# usb_uart.net
KiCad netlist of a schematic drawn in Altium Designer
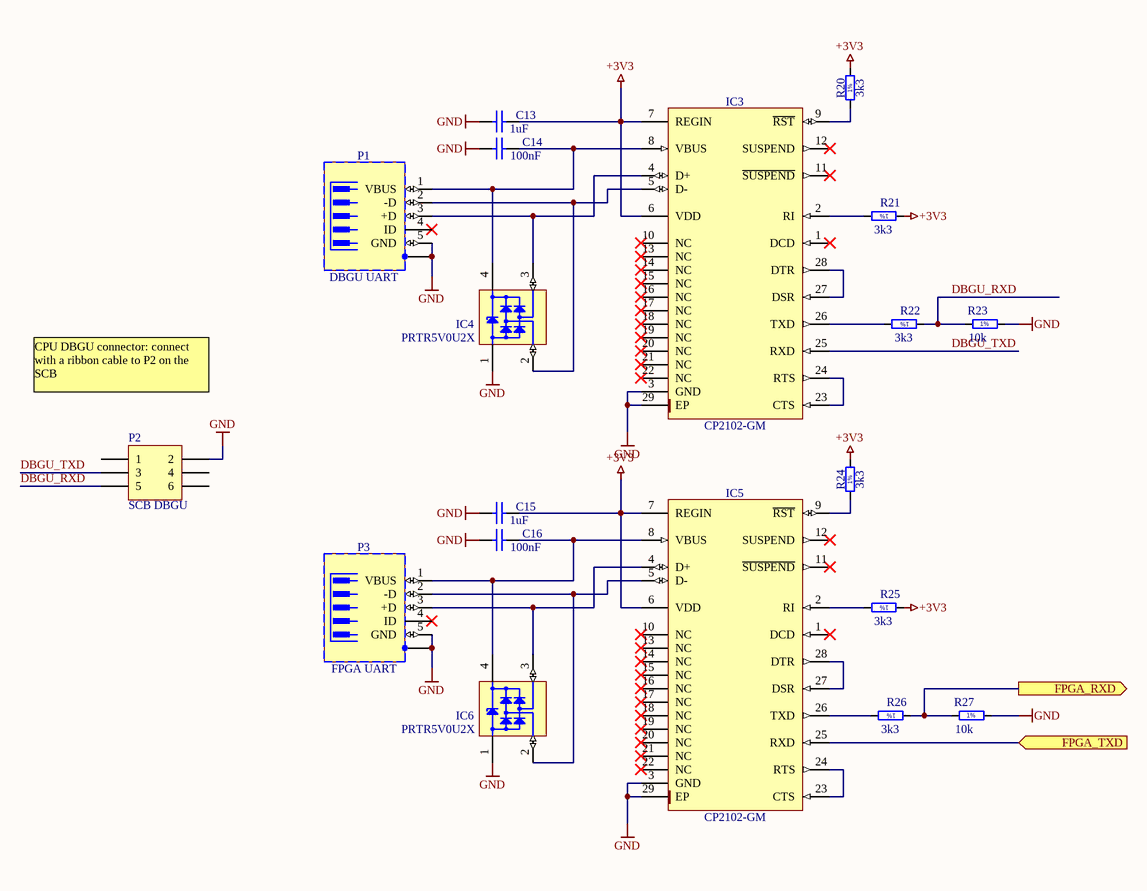
[diagram p0: usb_uart.SchDoc]

(export (version "E")
  (design (tool "Eeschema 10.0.6"))
  (components
    (comp (ref "C13")
      (value "1uF")
      (footprint "CAPC1608X87N")
      (description "Non-polarised capacitor")
      (fields
        (field (name "PART NUMBER") "CC0603_1UF_16V_10%_X7R")
        (field (name "VOLTAGE") "16V")
        (field (name "AUTHOR") "CERN DEM JLC")
      )
      (libsource (lib "Capacitors") (part "Capacitor - non polarized"))
    )
    (comp (ref "C14")
      (value "100nF")
      (footprint "CAPC1608X87N")
      (description "Non-polarised capacitor")
      (fields
        (field (name "PART NUMBER") "CC0603_100NF_50V_10%_X7R")
        (field (name "VOLTAGE") "50V")
        (field (name "AUTHOR") "CERN DEM JLC")
      )
      (libsource (lib "Capacitors") (part "Capacitor - non polarized"))
    )
    (comp (ref "C15")
      (value "1uF")
      (footprint "CAPC1608X87N")
      (description "Non-polarised capacitor")
      (fields
        (field (name "PART NUMBER") "CC0603_1UF_16V_10%_X7R")
        (field (name "VOLTAGE") "16V")
        (field (name "AUTHOR") "CERN DEM JLC")
      )
      (libsource (lib "Capacitors") (part "Capacitor - non polarized"))
    )
    (comp (ref "C16")
      (value "100nF")
      (footprint "CAPC1608X87N")
      (description "Non-polarised capacitor")
      (fields
        (field (name "PART NUMBER") "CC0603_100NF_50V_10%_X7R")
        (field (name "VOLTAGE") "50V")
        (field (name "AUTHOR") "CERN DEM JLC")
      )
      (libsource (lib "Capacitors") (part "Capacitor - non polarized"))
    )
    (comp (ref "IC3")
      (value "CP2102-GM")
      (footprint "QFN50P500X500X100-29N-S335")
      (description "Single-Chip USB to UART Bridge")
      (fields (field (name "MANUFACTURER") "SILICON LABS") (field (name "AUTHOR") "CERN DEM JLC"))
      (libsource (lib "ICs And Semiconductors") (part "CP2102-GM"))
    )
    (comp (ref "IC4")
      (value "PRTR5V0U2X")
      (footprint "SOT190P230X110-4N")
      (description "Ultra Low Capacitance Double Rail-to-Rail ESD Protection Diode")
      (fields
        (field (name "VOLTAGE") "5.5V")
        (field (name "MANUFACTURER") "PHILIPS NXP")
        (field (name "AUTHOR") "CERN DEM JLC")
      )
      (libsource (lib "ICs And Semiconductors") (part "PRTR5V0U2X"))
    )
    (comp (ref "IC5")
      (value "CP2102-GM")
      (footprint "QFN50P500X500X100-29N-S335")
      (description "Single-Chip USB to UART Bridge")
      (fields (field (name "MANUFACTURER") "SILICON LABS") (field (name "AUTHOR") "CERN DEM JLC"))
      (libsource (lib "ICs And Semiconductors") (part "CP2102-GM"))
    )
    (comp (ref "IC6")
      (value "PRTR5V0U2X")
      (footprint "SOT190P230X110-4N")
      (description "Ultra Low Capacitance Double Rail-to-Rail ESD Protection Diode")
      (fields
        (field (name "VOLTAGE") "5.5V")
        (field (name "MANUFACTURER") "PHILIPS NXP")
        (field (name "AUTHOR") "CERN DEM JLC")
      )
      (libsource (lib "ICs And Semiconductors") (part "PRTR5V0U2X"))
    )
    (comp (ref "P1")
      (value "DBGU UART")
      (footprint "TYCO_1734035-1")
      (description "5 Pin + 1 Shield USB Receptacle")
      (fields
        (field (name "PART NUMBER") "TYCO_1734035-1")
        (field (name "MANUFACTURER") "TYCO ELECTRONICS")
        (field (name "AUTHOR") "CERN DEM JLC")
      )
      (libsource (lib "Connectors") (part "Connector USB 5 Pin + 1Shield"))
    )
    (comp (ref "P2")
      (value "SCB DBGU")
      (footprint "HDR2X3")
      (description "Header, 3-Pin, Dual row, 2.54mm pitch")
      (fields (field (name "PUBLISHER") "Altium Limited"))
      (libsource (lib "Miscellaneous Connectors") (part "MHDR2X3"))
    )
    (comp (ref "P3")
      (value "FPGA UART")
      (footprint "TYCO_1734035-1")
      (description "5 Pin + 1 Shield USB Receptacle")
      (fields
        (field (name "PART NUMBER") "TYCO_1734035-1")
        (field (name "MANUFACTURER") "TYCO ELECTRONICS")
        (field (name "AUTHOR") "CERN DEM JLC")
      )
      (libsource (lib "Connectors") (part "Connector USB 5 Pin + 1Shield"))
    )
    (comp (ref "R20")
      (value "3k3")
      (footprint "RESC1608X55N")
      (description "Resistor - 1%")
      (fields
        (field (name "PART NUMBER") "R0603_3K3_1%_0.1W_100PPM")
        (field (name "POWER") "0.1W")
        (field (name "AUTHOR") "CERN DEM JLC")
      )
      (libsource (lib "Resistors") (part "Resistor - 1%"))
    )
    (comp (ref "R21")
      (value "3k3")
      (footprint "RESC1608X55N")
      (description "Resistor - 1%")
      (fields
        (field (name "PART NUMBER") "R0603_3K3_1%_0.1W_100PPM")
        (field (name "POWER") "0.1W")
        (field (name "AUTHOR") "CERN DEM JLC")
      )
      (libsource (lib "Resistors") (part "Resistor - 1%"))
    )
    (comp (ref "R22")
      (value "3k3")
      (footprint "RESC1608X55N")
      (description "Resistor - 1%")
      (fields
        (field (name "PART NUMBER") "R0603_3K3_1%_0.1W_100PPM")
        (field (name "POWER") "0.1W")
        (field (name "AUTHOR") "CERN DEM JLC")
      )
      (libsource (lib "Resistors") (part "Resistor - 1%"))
    )
    (comp (ref "R23")
      (value "10k")
      (footprint "RESC1608X55N")
      (description "Resistor - 1%")
      (fields
        (field (name "PART NUMBER") "R0603_10K_1%_0.1W_100PPM")
        (field (name "POWER") "0.1W")
        (field (name "AUTHOR") "CERN DEM JLC")
      )
      (libsource (lib "Resistors") (part "Resistor - 1%"))
    )
    (comp (ref "R24")
      (value "3k3")
      (footprint "RESC1608X55N")
      (description "Resistor - 1%")
      (fields
        (field (name "PART NUMBER") "R0603_3K3_1%_0.1W_100PPM")
        (field (name "POWER") "0.1W")
        (field (name "AUTHOR") "CERN DEM JLC")
      )
      (libsource (lib "Resistors") (part "Resistor - 1%"))
    )
    (comp (ref "R25")
      (value "3k3")
      (footprint "RESC1608X55N")
      (description "Resistor - 1%")
      (fields
        (field (name "PART NUMBER") "R0603_3K3_1%_0.1W_100PPM")
        (field (name "POWER") "0.1W")
        (field (name "AUTHOR") "CERN DEM JLC")
      )
      (libsource (lib "Resistors") (part "Resistor - 1%"))
    )
    (comp (ref "R26")
      (value "3k3")
      (footprint "RESC1608X55N")
      (description "Resistor - 1%")
      (fields
        (field (name "PART NUMBER") "R0603_3K3_1%_0.1W_100PPM")
        (field (name "POWER") "0.1W")
        (field (name "AUTHOR") "CERN DEM JLC")
      )
      (libsource (lib "Resistors") (part "Resistor - 1%"))
    )
    (comp (ref "R27")
      (value "10k")
      (footprint "RESC1608X55N")
      (description "Resistor - 1%")
      (fields
        (field (name "PART NUMBER") "R0603_10K_1%_0.1W_100PPM")
        (field (name "POWER") "0.1W")
        (field (name "AUTHOR") "CERN DEM JLC")
      )
      (libsource (lib "Resistors") (part "Resistor - 1%"))
    )
  )
  (nets
    (net (code "1") (name "+3V3") (class "Default")
      (node (ref "C13") (pin "1") (pinfunction "1_1") (pintype "passive"))
      (node (ref "C15") (pin "1") (pinfunction "1_1") (pintype "passive"))
      (node (ref "IC3") (pin "6") (pinfunction "VDD_6") (pintype "power_in"))
      (node (ref "IC3") (pin "7") (pinfunction "REGIN_7") (pintype "power_in"))
      (node (ref "IC5") (pin "6") (pinfunction "VDD_6") (pintype "power_in"))
      (node (ref "IC5") (pin "7") (pinfunction "REGIN_7") (pintype "power_in"))
      (node (ref "R20") (pin "2") (pinfunction "2_2") (pintype "passive"))
      (node (ref "R21") (pin "1") (pinfunction "1_1") (pintype "passive"))
      (node (ref "R24") (pin "2") (pinfunction "2_2") (pintype "passive"))
      (node (ref "R25") (pin "1") (pinfunction "1_1") (pintype "passive"))
    )
    (net (code "2") (name "/DBGU_RXD") (class "Default")
      (node (ref "P2") (pin "5") (pinfunction "5_5") (pintype "passive"))
      (node (ref "R22") (pin "1") (pinfunction "1_1") (pintype "passive"))
      (node (ref "R23") (pin "1") (pinfunction "1_1") (pintype "passive"))
    )
    (net (code "3") (name "/DBGU_TXD") (class "Default")
      (node (ref "IC3") (pin "25") (pinfunction "RXD_25") (pintype "input"))
      (node (ref "P2") (pin "3") (pinfunction "3_3") (pintype "passive"))
    )
    (net (code "4") (name "/FPGA_RXD") (class "Default")
      (node (ref "R26") (pin "1") (pinfunction "1_1") (pintype "passive"))
      (node (ref "R27") (pin "1") (pinfunction "1_1") (pintype "passive"))
    )
    (net (code "5") (name "/FPGA_TXD") (class "Default")
      (node (ref "IC5") (pin "25") (pinfunction "RXD_25") (pintype "input"))
    )
    (net (code "6") (name "GND") (class "Default")
      (node (ref "C13") (pin "2") (pinfunction "2_2") (pintype "passive"))
      (node (ref "C14") (pin "2") (pinfunction "2_2") (pintype "passive"))
      (node (ref "C15") (pin "2") (pinfunction "2_2") (pintype "passive"))
      (node (ref "C16") (pin "2") (pinfunction "2_2") (pintype "passive"))
      (node (ref "IC3") (pin "29") (pinfunction "EP_29") (pintype "power_in"))
      (node (ref "IC3") (pin "3") (pinfunction "GND_3") (pintype "power_in"))
      (node (ref "IC4") (pin "1") (pinfunction "GND_1") (pintype "power_in"))
      (node (ref "IC5") (pin "29") (pinfunction "EP_29") (pintype "power_in"))
      (node (ref "IC5") (pin "3") (pinfunction "GND_3") (pintype "power_in"))
      (node (ref "IC6") (pin "1") (pinfunction "GND_1") (pintype "power_in"))
      (node (ref "P1") (pin "5") (pinfunction "GND_5") (pintype "bidirectional"))
      (node (ref "P1") (pin "6") (pinfunction "SH_6") (pintype "power_in"))
      (node (ref "P2") (pin "2") (pinfunction "2_2") (pintype "passive"))
      (node (ref "P3") (pin "5") (pinfunction "GND_5") (pintype "bidirectional"))
      (node (ref "P3") (pin "6") (pinfunction "SH_6") (pintype "power_in"))
      (node (ref "R23") (pin "2") (pinfunction "2_2") (pintype "passive"))
      (node (ref "R27") (pin "2") (pinfunction "2_2") (pintype "passive"))
    )
    (net (code "7") (name "Net-(IC3-CTS)") (class "Default")
      (node (ref "IC3") (pin "23") (pinfunction "CTS_23") (pintype "input"))
      (node (ref "IC3") (pin "24") (pinfunction "RTS_24") (pintype "output"))
    )
    (net (code "8") (name "Net-(IC3-D+)") (class "Default")
      (node (ref "IC3") (pin "4") (pinfunction "D+_4") (pintype "bidirectional"))
      (node (ref "IC4") (pin "3") (pinfunction "I/O2_3") (pintype "bidirectional"))
      (node (ref "P1") (pin "3") (pinfunction "+D_3") (pintype "bidirectional"))
    )
    (net (code "9") (name "Net-(IC3-D-)") (class "Default")
      (node (ref "IC3") (pin "5") (pinfunction "D-_5") (pintype "bidirectional"))
      (node (ref "IC4") (pin "2") (pinfunction "I/O1_2") (pintype "bidirectional"))
      (node (ref "P1") (pin "2") (pinfunction "-D_2") (pintype "bidirectional"))
    )
    (net (code "10") (name "Net-(IC3-DSR)") (class "Default")
      (node (ref "IC3") (pin "27") (pinfunction "DSR_27") (pintype "input"))
      (node (ref "IC3") (pin "28") (pinfunction "DTR_28") (pintype "output"))
    )
    (net (code "11") (name "Net-(IC3-RI)") (class "Default")
      (node (ref "IC3") (pin "2") (pinfunction "RI_2") (pintype "input"))
      (node (ref "R21") (pin "2") (pinfunction "2_2") (pintype "passive"))
    )
    (net (code "12") (name "Net-(IC3-TXD)") (class "Default")
      (node (ref "IC3") (pin "26") (pinfunction "TXD_26") (pintype "output"))
      (node (ref "R22") (pin "2") (pinfunction "2_2") (pintype "passive"))
    )
    (net (code "13") (name "Net-(IC3-VBUS)") (class "Default")
      (node (ref "C14") (pin "1") (pinfunction "1_1") (pintype "passive"))
      (node (ref "IC3") (pin "8") (pinfunction "VBUS_8") (pintype "input"))
      (node (ref "IC4") (pin "4") (pinfunction "VCC_4") (pintype "power_in"))
      (node (ref "P1") (pin "1") (pinfunction "VBUS_1") (pintype "bidirectional"))
    )
    (net (code "14") (name "Net-(IC3-~{RST})") (class "Default")
      (node (ref "IC3") (pin "9") (pinfunction "~{RST}_9") (pintype "bidirectional"))
      (node (ref "R20") (pin "1") (pinfunction "1_1") (pintype "passive"))
    )
    (net (code "15") (name "Net-(IC5-CTS)") (class "Default")
      (node (ref "IC5") (pin "23") (pinfunction "CTS_23") (pintype "input"))
      (node (ref "IC5") (pin "24") (pinfunction "RTS_24") (pintype "output"))
    )
    (net (code "16") (name "Net-(IC5-D+)") (class "Default")
      (node (ref "IC5") (pin "4") (pinfunction "D+_4") (pintype "bidirectional"))
      (node (ref "IC6") (pin "3") (pinfunction "I/O2_3") (pintype "bidirectional"))
      (node (ref "P3") (pin "3") (pinfunction "+D_3") (pintype "bidirectional"))
    )
    (net (code "17") (name "Net-(IC5-D-)") (class "Default")
      (node (ref "IC5") (pin "5") (pinfunction "D-_5") (pintype "bidirectional"))
      (node (ref "IC6") (pin "2") (pinfunction "I/O1_2") (pintype "bidirectional"))
      (node (ref "P3") (pin "2") (pinfunction "-D_2") (pintype "bidirectional"))
    )
    (net (code "18") (name "Net-(IC5-DSR)") (class "Default")
      (node (ref "IC5") (pin "27") (pinfunction "DSR_27") (pintype "input"))
      (node (ref "IC5") (pin "28") (pinfunction "DTR_28") (pintype "output"))
    )
    (net (code "19") (name "Net-(IC5-RI)") (class "Default")
      (node (ref "IC5") (pin "2") (pinfunction "RI_2") (pintype "input"))
      (node (ref "R25") (pin "2") (pinfunction "2_2") (pintype "passive"))
    )
    (net (code "20") (name "Net-(IC5-TXD)") (class "Default")
      (node (ref "IC5") (pin "26") (pinfunction "TXD_26") (pintype "output"))
      (node (ref "R26") (pin "2") (pinfunction "2_2") (pintype "passive"))
    )
    (net (code "21") (name "Net-(IC5-VBUS)") (class "Default")
      (node (ref "C16") (pin "1") (pinfunction "1_1") (pintype "passive"))
      (node (ref "IC5") (pin "8") (pinfunction "VBUS_8") (pintype "input"))
      (node (ref "IC6") (pin "4") (pinfunction "VCC_4") (pintype "power_in"))
      (node (ref "P3") (pin "1") (pinfunction "VBUS_1") (pintype "bidirectional"))
    )
    (net (code "22") (name "Net-(IC5-~{RST})") (class "Default")
      (node (ref "IC5") (pin "9") (pinfunction "~{RST}_9") (pintype "bidirectional"))
      (node (ref "R24") (pin "1") (pinfunction "1_1") (pintype "passive"))
    )
    (net (code "23") (name "unconnected-(IC3-DCD-Pad1)") (class "Default")
      (node (ref "IC3") (pin "1") (pinfunction "DCD_1") (pintype "input+no_connect"))
    )
    (net (code "24") (name "unconnected-(IC3-NC-Pad10)") (class "Default")
      (node (ref "IC3") (pin "10") (pinfunction "NC_10") (pintype "passive+no_connect"))
    )
    (net (code "25") (name "unconnected-(IC3-NC-Pad13)") (class "Default")
      (node (ref "IC3") (pin "13") (pinfunction "NC_13") (pintype "passive+no_connect"))
    )
    (net (code "26") (name "unconnected-(IC3-NC-Pad14)") (class "Default")
      (node (ref "IC3") (pin "14") (pinfunction "NC_14") (pintype "passive+no_connect"))
    )
    (net (code "27") (name "unconnected-(IC3-NC-Pad15)") (class "Default")
      (node (ref "IC3") (pin "15") (pinfunction "NC_15") (pintype "passive+no_connect"))
    )
    (net (code "28") (name "unconnected-(IC3-NC-Pad16)") (class "Default")
      (node (ref "IC3") (pin "16") (pinfunction "NC_16") (pintype "passive+no_connect"))
    )
    (net (code "29") (name "unconnected-(IC3-NC-Pad17)") (class "Default")
      (node (ref "IC3") (pin "17") (pinfunction "NC_17") (pintype "passive+no_connect"))
    )
    (net (code "30") (name "unconnected-(IC3-NC-Pad18)") (class "Default")
      (node (ref "IC3") (pin "18") (pinfunction "NC_18") (pintype "passive+no_connect"))
    )
    (net (code "31") (name "unconnected-(IC3-NC-Pad19)") (class "Default")
      (node (ref "IC3") (pin "19") (pinfunction "NC_19") (pintype "passive+no_connect"))
    )
    (net (code "32") (name "unconnected-(IC3-NC-Pad20)") (class "Default")
      (node (ref "IC3") (pin "20") (pinfunction "NC_20") (pintype "passive+no_connect"))
    )
    (net (code "33") (name "unconnected-(IC3-NC-Pad21)") (class "Default")
      (node (ref "IC3") (pin "21") (pinfunction "NC_21") (pintype "passive+no_connect"))
    )
    (net (code "34") (name "unconnected-(IC3-NC-Pad22)") (class "Default")
      (node (ref "IC3") (pin "22") (pinfunction "NC_22") (pintype "passive+no_connect"))
    )
    (net (code "35") (name "unconnected-(IC3-SUSPEND-Pad12)") (class "Default")
      (node (ref "IC3") (pin "12") (pinfunction "SUSPEND_12") (pintype "output+no_connect"))
    )
    (net (code "36") (name "unconnected-(IC3-~{SUSPEND}-Pad11)") (class "Default")
      (node (ref "IC3") (pin "11") (pinfunction "~{SUSPEND}_11") (pintype "output+no_connect"))
    )
    (net (code "37") (name "unconnected-(IC5-DCD-Pad1)") (class "Default")
      (node (ref "IC5") (pin "1") (pinfunction "DCD_1") (pintype "input+no_connect"))
    )
    (net (code "38") (name "unconnected-(IC5-NC-Pad10)") (class "Default")
      (node (ref "IC5") (pin "10") (pinfunction "NC_10") (pintype "passive+no_connect"))
    )
    (net (code "39") (name "unconnected-(IC5-NC-Pad13)") (class "Default")
      (node (ref "IC5") (pin "13") (pinfunction "NC_13") (pintype "passive+no_connect"))
    )
    (net (code "40") (name "unconnected-(IC5-NC-Pad14)") (class "Default")
      (node (ref "IC5") (pin "14") (pinfunction "NC_14") (pintype "passive+no_connect"))
    )
    (net (code "41") (name "unconnected-(IC5-NC-Pad15)") (class "Default")
      (node (ref "IC5") (pin "15") (pinfunction "NC_15") (pintype "passive+no_connect"))
    )
    (net (code "42") (name "unconnected-(IC5-NC-Pad16)") (class "Default")
      (node (ref "IC5") (pin "16") (pinfunction "NC_16") (pintype "passive+no_connect"))
    )
    (net (code "43") (name "unconnected-(IC5-NC-Pad17)") (class "Default")
      (node (ref "IC5") (pin "17") (pinfunction "NC_17") (pintype "passive+no_connect"))
    )
    (net (code "44") (name "unconnected-(IC5-NC-Pad18)") (class "Default")
      (node (ref "IC5") (pin "18") (pinfunction "NC_18") (pintype "passive+no_connect"))
    )
    (net (code "45") (name "unconnected-(IC5-NC-Pad19)") (class "Default")
      (node (ref "IC5") (pin "19") (pinfunction "NC_19") (pintype "passive+no_connect"))
    )
    (net (code "46") (name "unconnected-(IC5-NC-Pad20)") (class "Default")
      (node (ref "IC5") (pin "20") (pinfunction "NC_20") (pintype "passive+no_connect"))
    )
    (net (code "47") (name "unconnected-(IC5-NC-Pad21)") (class "Default")
      (node (ref "IC5") (pin "21") (pinfunction "NC_21") (pintype "passive+no_connect"))
    )
    (net (code "48") (name "unconnected-(IC5-NC-Pad22)") (class "Default")
      (node (ref "IC5") (pin "22") (pinfunction "NC_22") (pintype "passive+no_connect"))
    )
    (net (code "49") (name "unconnected-(IC5-SUSPEND-Pad12)") (class "Default")
      (node (ref "IC5") (pin "12") (pinfunction "SUSPEND_12") (pintype "output+no_connect"))
    )
    (net (code "50") (name "unconnected-(IC5-~{SUSPEND}-Pad11)") (class "Default")
      (node (ref "IC5") (pin "11") (pinfunction "~{SUSPEND}_11") (pintype "output+no_connect"))
    )
    (net (code "51") (name "unconnected-(P1-ID-Pad4)") (class "Default")
      (node (ref "P1") (pin "4") (pinfunction "ID_4") (pintype "passive+no_connect"))
    )
    (net (code "52") (name "unconnected-(P2-Pad1)") (class "Default")
      (node (ref "P2") (pin "1") (pinfunction "1_1") (pintype "passive"))
    )
    (net (code "53") (name "unconnected-(P2-Pad4)") (class "Default")
      (node (ref "P2") (pin "4") (pinfunction "4_4") (pintype "passive"))
    )
    (net (code "54") (name "unconnected-(P2-Pad6)") (class "Default")
      (node (ref "P2") (pin "6") (pinfunction "6_6") (pintype "passive"))
    )
    (net (code "55") (name "unconnected-(P3-ID-Pad4)") (class "Default")
      (node (ref "P3") (pin "4") (pinfunction "ID_4") (pintype "passive+no_connect"))
    )
  )
)
